# 4_Current_Sensing.net
KiCad netlist of a schematic drawn in Altium Designer
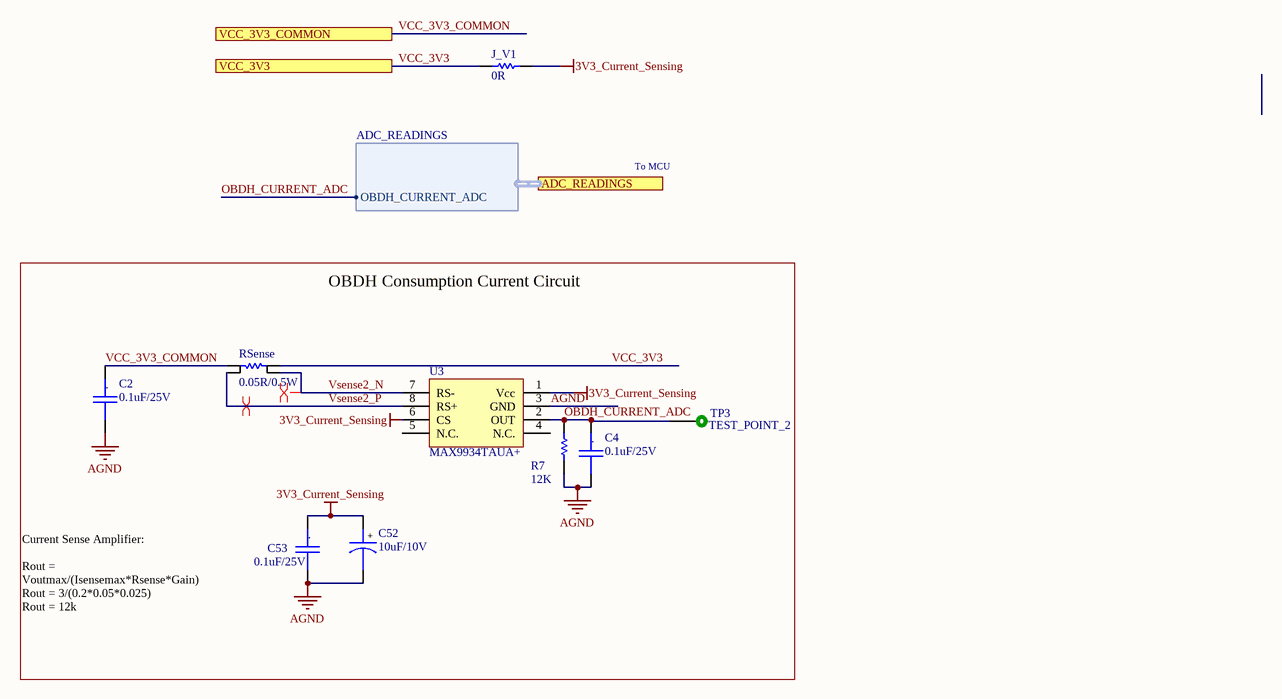
[diagram p0: 4_Current_Sensing.SchDoc]

(export (version "E")
  (design (tool "Eeschema 10.0.6"))
  (components
    (comp (ref "C2")
      (value "0.1uF/25V")
      (footprint "CC0805")
      (description "CAP CER 0.1UF 25V 10% X7R 0805")
      (fields (field (name "PARTNUMBER") "CC0805KRX7R8BB104"))
      (libsource (lib "OBDH_Eng_Model_2_ALT") (part "Cap_Cer_X7R_0.1uF_25V_0805"))
    )
    (comp (ref "C4")
      (value "0.1uF/25V")
      (footprint "CC0805")
      (description "CAP CER 0.1UF 25V 10% X7R 0805")
      (fields (field (name "PARTNUMBER") "CC0805KRX7R8BB104"))
      (libsource (lib "OBDH_Eng_Model_2_ALT") (part "Cap_Cer_X7R_0.1uF_25V_0805"))
    )
    (comp (ref "C52")
      (value "10uF/10V")
      (footprint "CC0805_Tantalum")
      (description "CAP Tantalum 10uF 10V 20% 0805")
      (fields (field (name "PARTNUMBER") "TPSP106M010R2000"))
      (libsource (lib "OBDH_Eng_Model_2_ALT") (part "Cap_Tant_SMD_10uF_10V_0805"))
    )
    (comp (ref "C53")
      (value "0.1uF/25V")
      (footprint "CC0805")
      (description "CAP CER 0.1UF 25V 10% X7R 0805")
      (fields (field (name "PARTNUMBER") "CC0805KRX7R8BB104"))
      (libsource (lib "OBDH_Eng_Model_2_ALT") (part "Cap_Cer_X7R_0.1uF_25V_0805"))
    )
    (comp (ref "J_V1")
      (value "0R")
      (footprint "0805")
      (description "RES 0R OHM 1/16W JUMPER 0805")
      (fields (field (name "PARTNUMBER") "CRCW08050000Z0EA"))
      (libsource (lib "OBDH_Eng_Model_2_ALT") (part "R0R_JUMPER_1/16W_0805"))
    )
    (comp (ref "R7")
      (value "12K")
      (footprint "0805")
      (description "RES 1.65K OHM 1/10W 0.1% 0805")
      (fields (field (name "PARTNUMBER") "PCF0805R-1K65BT1"))
      (libsource (lib "OBDH_Eng_Model_2_ALT") (part "R1.65K_1%_1/10W_0805"))
    )
    (comp (ref "RSense")
      (value "0.05R/0.5W")
      (footprint "1206 - ohmite")
      (description "Current Sense Resistors - SMD 0.05ohm .5% 4 Terminal")
      (fields (field (name "PARTNUMBER") "LVK12R050DER"))
      (libsource (lib "OBDH_Eng_Model_2_ALT") (part "R0.05R_0.5%_0.5W_1206"))
    )
    (comp (ref "TP3")
      (value "TEST_POINT_2")
      (footprint "TEST_POINT_2")
      (description "Test point")
      (libsource (lib "OBDH_Eng_Model_2_ALT") (part "TEST_POINT_2"))
    )
    (comp (ref "U3")
      (value "MAX9934TAUA+")
      (footprint "MSOP-8")
      (libsource (lib "OBDH_Eng_Model_2_ALT") (part "MAX9934TAUA+"))
    )
  )
  (nets
    (net (code "2") (name "/OBDH_CURRENT_ADC") (class "Default")
      (node (ref "C4") (pin "1") (pinfunction "1_1") (pintype "passive"))
      (node (ref "R7") (pin "2") (pinfunction "2_2") (pintype "passive"))
      (node (ref "TP3") (pin "1") (pinfunction "1_1") (pintype "passive"))
      (node (ref "U3") (pin "2") (pinfunction "OUT_2") (pintype "passive"))
    )
    (net (code "3") (name "/VCC_3V3") (class "Default")
      (node (ref "J_V1") (pin "2") (pinfunction "2_2") (pintype "passive"))
      (node (ref "RSense") (pin "2") (pinfunction "2_2") (pintype "passive"))
    )
    (net (code "4") (name "/VCC_3V3_COMMON") (class "Default")
      (node (ref "C2") (pin "1") (pinfunction "1_1") (pintype "passive"))
      (node (ref "RSense") (pin "1") (pinfunction "1_1") (pintype "passive"))
    )
    (net (code "5") (name "/Vsense2_N") (class "Default")
      (node (ref "RSense") (pin "4") (pinfunction "4_4") (pintype "passive"))
      (node (ref "U3") (pin "7") (pinfunction "RS-_7") (pintype "passive"))
    )
    (net (code "6") (name "/Vsense2_P") (class "Default")
      (node (ref "RSense") (pin "3") (pinfunction "3_3") (pintype "passive"))
      (node (ref "U3") (pin "8") (pinfunction "RS+_8") (pintype "passive"))
    )
    (net (code "8") (name "3V3_Current_Sensing") (class "Default")
      (node (ref "C52") (pin "1") (pinfunction "1_1") (pintype "passive"))
      (node (ref "C53") (pin "1") (pinfunction "1_1") (pintype "passive"))
      (node (ref "J_V1") (pin "1") (pinfunction "1_1") (pintype "passive"))
      (node (ref "U3") (pin "1") (pinfunction "Vcc_1") (pintype "passive"))
      (node (ref "U3") (pin "6") (pinfunction "CS_6") (pintype "passive"))
    )
    (net (code "9") (name "AGND") (class "Default")
      (node (ref "C2") (pin "2") (pinfunction "2_2") (pintype "passive"))
      (node (ref "C4") (pin "2") (pinfunction "2_2") (pintype "passive"))
      (node (ref "C52") (pin "2") (pinfunction "2_2") (pintype "passive"))
      (node (ref "C53") (pin "2") (pinfunction "2_2") (pintype "passive"))
      (node (ref "R7") (pin "1") (pinfunction "1_1") (pintype "passive"))
      (node (ref "U3") (pin "3") (pinfunction "GND_3") (pintype "passive"))
    )
    (net (code "10") (name "unconnected-(U3-N.C.-Pad4)") (class "Default")
      (node (ref "U3") (pin "4") (pinfunction "N.C._4") (pintype "passive"))
    )
    (net (code "11") (name "unconnected-(U3-N.C.-Pad5)") (class "Default")
      (node (ref "U3") (pin "5") (pinfunction "N.C._5") (pintype "passive"))
    )
  )
)
